# 07-I225-2.net
KiCad netlist of a schematic drawn in Altium Designer
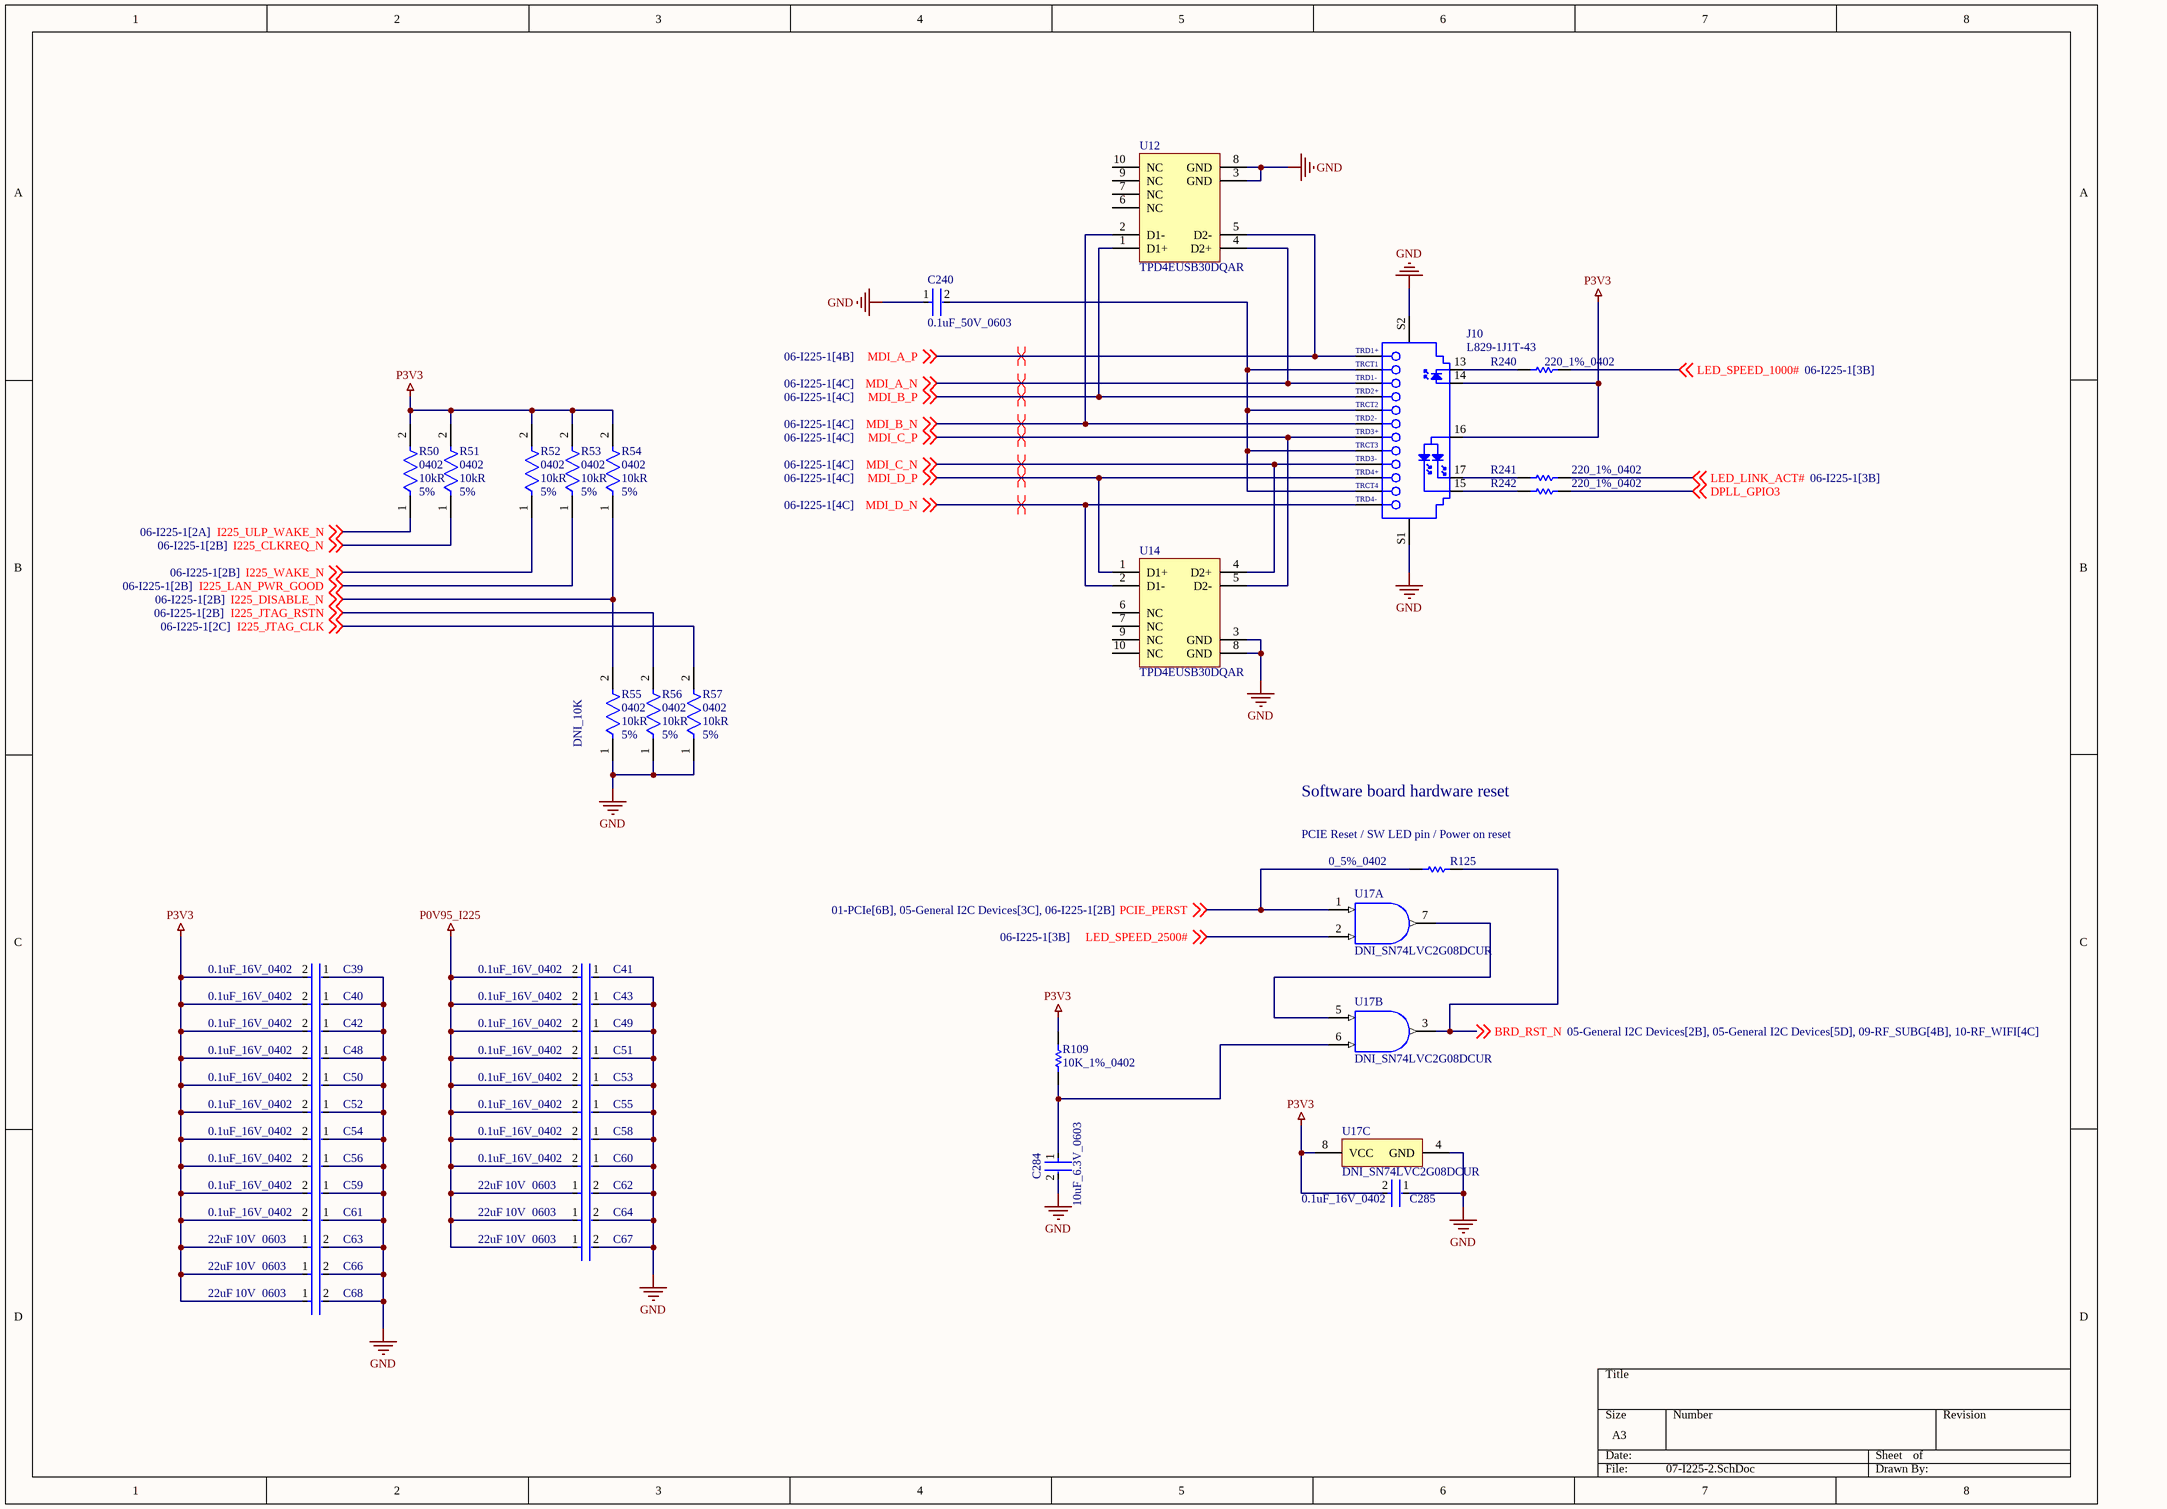
[diagram p0: 07-I225-2.SchDoc]

(export (version "E")
  (design (tool "Eeschema 10.0.6"))
  (components
    (comp (ref "C39")
      (value "0.1uF_16V_0402")
      (footprint "FP-GRM15-MFG")
      (description "CAP CER 0.1UF 16V X7R 0402")
      (fields (field (name "MANUFACTURER PART NUMBER") "GRM155R71C104KA88D") (field (name "TOLERANCE") "10%"))
      (libsource (lib "Altium Content Vault") (part "236180d848d6139a670b325ea6854c9"))
    )
    (comp (ref "C40")
      (value "0.1uF_16V_0402")
      (footprint "FP-GRM15-MFG")
      (description "CAP CER 0.1UF 16V X7R 0402")
      (fields (field (name "MANUFACTURER PART NUMBER") "GRM155R71C104KA88D") (field (name "TOLERANCE") "10%"))
      (libsource (lib "Altium Content Vault") (part "236180d848d6139a670b325ea6854c9"))
    )
    (comp (ref "C41")
      (value "0.1uF_16V_0402")
      (footprint "FP-GRM15-MFG")
      (description "CAP CER 0.1UF 16V X7R 0402")
      (fields (field (name "MANUFACTURER PART NUMBER") "GRM155R71C104KA88D") (field (name "TOLERANCE") "10%"))
      (libsource (lib "Altium Content Vault") (part "236180d848d6139a670b325ea6854c9"))
    )
    (comp (ref "C42")
      (value "0.1uF_16V_0402")
      (footprint "FP-GRM15-MFG")
      (description "CAP CER 0.1UF 16V X7R 0402")
      (fields (field (name "MANUFACTURER PART NUMBER") "GRM155R71C104KA88D") (field (name "TOLERANCE") "10%"))
      (libsource (lib "Altium Content Vault") (part "236180d848d6139a670b325ea6854c9"))
    )
    (comp (ref "C43")
      (value "0.1uF_16V_0402")
      (footprint "FP-GRM15-MFG")
      (description "CAP CER 0.1UF 16V X7R 0402")
      (fields (field (name "MANUFACTURER PART NUMBER") "GRM155R71C104KA88D") (field (name "TOLERANCE") "10%"))
      (libsource (lib "Altium Content Vault") (part "236180d848d6139a670b325ea6854c9"))
    )
    (comp (ref "C48")
      (value "0.1uF_16V_0402")
      (footprint "FP-GRM15-MFG")
      (description "CAP CER 0.1UF 16V X7R 0402")
      (fields (field (name "MANUFACTURER PART NUMBER") "GRM155R71C104KA88D") (field (name "TOLERANCE") "10%"))
      (libsource (lib "Altium Content Vault") (part "236180d848d6139a670b325ea6854c9"))
    )
    (comp (ref "C49")
      (value "0.1uF_16V_0402")
      (footprint "FP-GRM15-MFG")
      (description "CAP CER 0.1UF 16V X7R 0402")
      (fields (field (name "MANUFACTURER PART NUMBER") "GRM155R71C104KA88D") (field (name "TOLERANCE") "10%"))
      (libsource (lib "Altium Content Vault") (part "236180d848d6139a670b325ea6854c9"))
    )
    (comp (ref "C50")
      (value "0.1uF_16V_0402")
      (footprint "FP-GRM15-MFG")
      (description "CAP CER 0.1UF 16V X7R 0402")
      (fields (field (name "MANUFACTURER PART NUMBER") "GRM155R71C104KA88D") (field (name "TOLERANCE") "10%"))
      (libsource (lib "Altium Content Vault") (part "236180d848d6139a670b325ea6854c9"))
    )
    (comp (ref "C51")
      (value "0.1uF_16V_0402")
      (footprint "FP-GRM15-MFG")
      (description "CAP CER 0.1UF 16V X7R 0402")
      (fields (field (name "MANUFACTURER PART NUMBER") "GRM155R71C104KA88D") (field (name "TOLERANCE") "10%"))
      (libsource (lib "Altium Content Vault") (part "236180d848d6139a670b325ea6854c9"))
    )
    (comp (ref "C52")
      (value "0.1uF_16V_0402")
      (footprint "FP-GRM15-MFG")
      (description "CAP CER 0.1UF 16V X7R 0402")
      (fields (field (name "MANUFACTURER PART NUMBER") "GRM155R71C104KA88D") (field (name "TOLERANCE") "10%"))
      (libsource (lib "Altium Content Vault") (part "236180d848d6139a670b325ea6854c9"))
    )
    (comp (ref "C53")
      (value "0.1uF_16V_0402")
      (footprint "FP-GRM15-MFG")
      (description "CAP CER 0.1UF 16V X7R 0402")
      (fields (field (name "MANUFACTURER PART NUMBER") "GRM155R71C104KA88D") (field (name "TOLERANCE") "10%"))
      (libsource (lib "Altium Content Vault") (part "236180d848d6139a670b325ea6854c9"))
    )
    (comp (ref "C54")
      (value "0.1uF_16V_0402")
      (footprint "FP-GRM15-MFG")
      (description "CAP CER 0.1UF 16V X7R 0402")
      (fields (field (name "MANUFACTURER PART NUMBER") "GRM155R71C104KA88D") (field (name "TOLERANCE") "10%"))
      (libsource (lib "Altium Content Vault") (part "236180d848d6139a670b325ea6854c9"))
    )
    (comp (ref "C55")
      (value "0.1uF_16V_0402")
      (footprint "FP-GRM15-MFG")
      (description "CAP CER 0.1UF 16V X7R 0402")
      (fields (field (name "MANUFACTURER PART NUMBER") "GRM155R71C104KA88D") (field (name "TOLERANCE") "10%"))
      (libsource (lib "Altium Content Vault") (part "236180d848d6139a670b325ea6854c9"))
    )
    (comp (ref "C56")
      (value "0.1uF_16V_0402")
      (footprint "FP-GRM15-MFG")
      (description "CAP CER 0.1UF 16V X7R 0402")
      (fields (field (name "MANUFACTURER PART NUMBER") "GRM155R71C104KA88D") (field (name "TOLERANCE") "10%"))
      (libsource (lib "Altium Content Vault") (part "236180d848d6139a670b325ea6854c9"))
    )
    (comp (ref "C58")
      (value "0.1uF_16V_0402")
      (footprint "FP-GRM15-MFG")
      (description "CAP CER 0.1UF 16V X7R 0402")
      (fields (field (name "MANUFACTURER PART NUMBER") "GRM155R71C104KA88D") (field (name "TOLERANCE") "10%"))
      (libsource (lib "Altium Content Vault") (part "236180d848d6139a670b325ea6854c9"))
    )
    (comp (ref "C59")
      (value "0.1uF_16V_0402")
      (footprint "FP-GRM15-MFG")
      (description "CAP CER 0.1UF 16V X7R 0402")
      (fields (field (name "MANUFACTURER PART NUMBER") "GRM155R71C104KA88D") (field (name "TOLERANCE") "10%"))
      (libsource (lib "Altium Content Vault") (part "236180d848d6139a670b325ea6854c9"))
    )
    (comp (ref "C60")
      (value "0.1uF_16V_0402")
      (footprint "FP-GRM15-MFG")
      (description "CAP CER 0.1UF 16V X7R 0402")
      (fields (field (name "MANUFACTURER PART NUMBER") "GRM155R71C104KA88D") (field (name "TOLERANCE") "10%"))
      (libsource (lib "Altium Content Vault") (part "236180d848d6139a670b325ea6854c9"))
    )
    (comp (ref "C61")
      (value "0.1uF_16V_0402")
      (footprint "FP-GRM15-MFG")
      (description "CAP CER 0.1UF 16V X7R 0402")
      (fields (field (name "MANUFACTURER PART NUMBER") "GRM155R71C104KA88D") (field (name "TOLERANCE") "10%"))
      (libsource (lib "Altium Content Vault") (part "236180d848d6139a670b325ea6854c9"))
    )
    (comp (ref "C62")
      (value "GRM188R61A226ME15D")
      (footprint "FP-GRM188-0_2-IPC_C")
      (description "Chip Multilayer Ceramic Capacitors for General Purpose, 0603, 22uF, X5R, 15%, 20%, 10V")
      (fields
        (field (name "TOLERANCE") "20%")
        (field (name "CAPACITANCE") "22uF")
        (field (name "VOLTAGE RATING") "10V")
        (field (name "CASE CODE (IMPERIAL)") "0603")
      )
      (libsource (lib "Altium Content Vault") (part "11868f565c42a9108669ba33697ecf6"))
    )
    (comp (ref "C63")
      (value "GRM188R61A226ME15D")
      (footprint "FP-GRM188-0_2-IPC_C")
      (description "Chip Multilayer Ceramic Capacitors for General Purpose, 0603, 22uF, X5R, 15%, 20%, 10V")
      (fields
        (field (name "TOLERANCE") "20%")
        (field (name "CAPACITANCE") "22uF")
        (field (name "VOLTAGE RATING") "10V")
        (field (name "CASE CODE (IMPERIAL)") "0603")
      )
      (libsource (lib "Altium Content Vault") (part "11868f565c42a9108669ba33697ecf6"))
    )
    (comp (ref "C64")
      (value "GRM188R61A226ME15D")
      (footprint "FP-GRM188-0_2-IPC_C")
      (description "Chip Multilayer Ceramic Capacitors for General Purpose, 0603, 22uF, X5R, 15%, 20%, 10V")
      (fields
        (field (name "TOLERANCE") "20%")
        (field (name "CAPACITANCE") "22uF")
        (field (name "VOLTAGE RATING") "10V")
        (field (name "CASE CODE (IMPERIAL)") "0603")
      )
      (libsource (lib "Altium Content Vault") (part "11868f565c42a9108669ba33697ecf6"))
    )
    (comp (ref "C66")
      (value "GRM188R61A226ME15D")
      (footprint "FP-GRM188-0_2-IPC_C")
      (description "Chip Multilayer Ceramic Capacitors for General Purpose, 0603, 22uF, X5R, 15%, 20%, 10V")
      (fields
        (field (name "TOLERANCE") "20%")
        (field (name "CAPACITANCE") "22uF")
        (field (name "VOLTAGE RATING") "10V")
        (field (name "CASE CODE (IMPERIAL)") "0603")
      )
      (libsource (lib "Altium Content Vault") (part "11868f565c42a9108669ba33697ecf6"))
    )
    (comp (ref "C67")
      (value "GRM188R61A226ME15D")
      (footprint "FP-GRM188-0_2-IPC_C")
      (description "Chip Multilayer Ceramic Capacitors for General Purpose, 0603, 22uF, X5R, 15%, 20%, 10V")
      (fields
        (field (name "TOLERANCE") "20%")
        (field (name "CAPACITANCE") "22uF")
        (field (name "VOLTAGE RATING") "10V")
        (field (name "CASE CODE (IMPERIAL)") "0603")
      )
      (libsource (lib "Altium Content Vault") (part "11868f565c42a9108669ba33697ecf6"))
    )
    (comp (ref "C68")
      (value "GRM188R61A226ME15D")
      (footprint "FP-GRM188-0_2-IPC_C")
      (description "Chip Multilayer Ceramic Capacitors for General Purpose, 0603, 22uF, X5R, 15%, 20%, 10V")
      (fields
        (field (name "TOLERANCE") "20%")
        (field (name "CAPACITANCE") "22uF")
        (field (name "VOLTAGE RATING") "10V")
        (field (name "CASE CODE (IMPERIAL)") "0603")
      )
      (libsource (lib "Altium Content Vault") (part "11868f565c42a9108669ba33697ecf6"))
    )
    (comp (ref "C240")
      (value "0.1uF_50V_0603")
      (footprint "FP-C0603-CJ-MFG")
      (description "CAP CER 0.1UF 50V X7R 0603")
      (fields (field (name "MANUFACTURER PART NUMBER") "C0603X104K5RACTU") (field (name "VOLTAGE") "50V"))
      (libsource (lib "Altium Content Vault") (part "11868f565c42a9108669ba33697ecf6"))
    )
    (comp (ref "C284")
      (value "10uF_6.3V_0603")
      (footprint "FP-C0603C106M9PACTU-MFG")
      (description "CAP CER 10UF 6.3V X5R 0603")
      (fields
        (field (name "MANUFACTURER PART NUMBER") "C0603C106M9PACTU")
        (field (name "MANUFACTURER") "Kemet")
      )
      (libsource (lib "Altium Content Vault") (part "b4654b650e69147ec39a6b967a45e02"))
    )
    (comp (ref "C285")
      (value "0.1uF_16V_0402")
      (footprint "FP-GRM15-MFG")
      (description "CAP CER 0.1UF 16V X7R 0402")
      (fields (field (name "MANUFACTURER PART NUMBER") "GRM155R71C104KA88D") (field (name "TOLERANCE") "10%"))
      (libsource (lib "Altium Content Vault") (part "236180d848d6139a670b325ea6854c9"))
    )
    (comp (ref "J10")
      (value "L829-1J1T-43")
      (footprint "BELS-L829-1J1T-43_V")
      (description "Gigabit MagJack(R) Ultra Low Profile, 10/100/1000 Base-T, 19-Pin THD, RoHS, Tray")
      (libsource (lib "Altium Content Vault") (part "RJ45-17-2SHLD"))
    )
    (comp (ref "R50")
      (value "CRCW040210K0JNED")
      (footprint "FP-CRCW0402-e3-IPC_B")
      (description "RES Thick Film, 10kΩ, 5%, 0.063W, 200ppm/°C, 0402")
      (fields
        (field (name "CASE/PACKAGE") "0402")
        (field (name "RESISTANCE") "10kR")
        (field (name "TOLERANCE") "5%")
      )
      (libsource (lib "Altium Content Vault") (part "1029c3af85768c4190bb7ad29bc67b5"))
    )
    (comp (ref "R51")
      (value "CRCW040210K0JNED")
      (footprint "FP-CRCW0402-e3-IPC_B")
      (description "RES Thick Film, 10kΩ, 5%, 0.063W, 200ppm/°C, 0402")
      (fields
        (field (name "CASE/PACKAGE") "0402")
        (field (name "RESISTANCE") "10kR")
        (field (name "TOLERANCE") "5%")
      )
      (libsource (lib "Altium Content Vault") (part "1029c3af85768c4190bb7ad29bc67b5"))
    )
    (comp (ref "R52")
      (value "CRCW040210K0JNED")
      (footprint "FP-CRCW0402-e3-IPC_B")
      (description "RES Thick Film, 10kΩ, 5%, 0.063W, 200ppm/°C, 0402")
      (fields
        (field (name "CASE/PACKAGE") "0402")
        (field (name "RESISTANCE") "10kR")
        (field (name "TOLERANCE") "5%")
      )
      (libsource (lib "Altium Content Vault") (part "1029c3af85768c4190bb7ad29bc67b5"))
    )
    (comp (ref "R53")
      (value "CRCW040210K0JNED")
      (footprint "FP-CRCW0402-e3-IPC_B")
      (description "RES Thick Film, 10kΩ, 5%, 0.063W, 200ppm/°C, 0402")
      (fields
        (field (name "CASE/PACKAGE") "0402")
        (field (name "RESISTANCE") "10kR")
        (field (name "TOLERANCE") "5%")
      )
      (libsource (lib "Altium Content Vault") (part "1029c3af85768c4190bb7ad29bc67b5"))
    )
    (comp (ref "R54")
      (value "CRCW040210K0JNED")
      (footprint "FP-CRCW0402-e3-IPC_B")
      (description "RES Thick Film, 10kΩ, 5%, 0.063W, 200ppm/°C, 0402")
      (fields
        (field (name "CASE/PACKAGE") "0402")
        (field (name "RESISTANCE") "10kR")
        (field (name "TOLERANCE") "5%")
      )
      (libsource (lib "Altium Content Vault") (part "1029c3af85768c4190bb7ad29bc67b5"))
    )
    (comp (ref "R55")
      (value "DNI_10K")
      (footprint "FP-CRCW0402-e3-IPC_B")
      (description "RES Thick Film, 10kΩ, 5%, 0.063W, 200ppm/°C, 0402")
      (fields
        (field (name "CASE/PACKAGE") "0402")
        (field (name "RESISTANCE") "10kR")
        (field (name "TOLERANCE") "5%")
      )
      (libsource (lib "Altium Content Vault") (part "1029c3af85768c4190bb7ad29bc67b5"))
    )
    (comp (ref "R56")
      (value "CRCW040210K0JNED")
      (footprint "FP-CRCW0402-e3-IPC_B")
      (description "RES Thick Film, 10kΩ, 5%, 0.063W, 200ppm/°C, 0402")
      (fields
        (field (name "CASE/PACKAGE") "0402")
        (field (name "RESISTANCE") "10kR")
        (field (name "TOLERANCE") "5%")
      )
      (libsource (lib "Altium Content Vault") (part "1029c3af85768c4190bb7ad29bc67b5"))
    )
    (comp (ref "R57")
      (value "CRCW040210K0JNED")
      (footprint "FP-CRCW0402-e3-IPC_B")
      (description "RES Thick Film, 10kΩ, 5%, 0.063W, 200ppm/°C, 0402")
      (fields
        (field (name "CASE/PACKAGE") "0402")
        (field (name "RESISTANCE") "10kR")
        (field (name "TOLERANCE") "5%")
      )
      (libsource (lib "Altium Content Vault") (part "1029c3af85768c4190bb7ad29bc67b5"))
    )
    (comp (ref "R109")
      (value "10K_1%_0402")
      (footprint "RESC1005X40X25NL10T10")
      (fields (field (name "MANUFACTURER") "Bourns") (field (name "PART NUMBER") "CR0402-FX-1002GLF"))
      (libsource (lib "Altium Content Vault") (part "RES"))
    )
    (comp (ref "R125")
      (value "0_5%_0402")
      (footprint "RESC1005X40X25LL10T10")
      (fields (field (name "MANUFACTURER") "KOA Speer") (field (name "PART NUMBER") "RK73Z1ETTP"))
      (libsource (lib "Altium Content Vault") (part "RES"))
    )
    (comp (ref "R240")
      (value "220_1%_0402")
      (footprint "RESC1005X40X25LL10T10")
      (fields (field (name "PART NUMBER") "RK73H1ETTP2200F") (field (name "MANUFACTURER") "KOA Speer"))
      (libsource (lib "Altium Content Vault") (part "RES"))
    )
    (comp (ref "R241")
      (value "220_1%_0402")
      (footprint "RESC1005X40X25LL10T10")
      (fields (field (name "PART NUMBER") "RK73H1ETTP2200F") (field (name "MANUFACTURER") "KOA Speer"))
      (libsource (lib "Altium Content Vault") (part "RES"))
    )
    (comp (ref "R242")
      (value "220_1%_0402")
      (footprint "RESC1005X40X25LL10T10")
      (fields (field (name "PART NUMBER") "RK73H1ETTP2200F") (field (name "MANUFACTURER") "KOA Speer"))
      (libsource (lib "Altium Content Vault") (part "RES"))
    )
    (comp (ref "U12")
      (value "TPD4EUSB30DQAR")
      (footprint "DQA0010A_V")
      (fields (field (name "MANUFACTURER") "Texas Instruments"))
      (libsource (lib "") (part "TI-TPD4EUSB30-SON_DQA-10_1"))
    )
    (comp (ref "U14")
      (value "TPD4EUSB30DQAR")
      (footprint "DQA0010A_V")
      (fields (field (name "MANUFACTURER") "Texas Instruments"))
      (libsource (lib "Altium Content Vault") (part "TI-TPD4EUSB30-SON_DQA-10"))
    )
    (comp (ref "U17")
      (value "DNI_SN74LVC2G08DCUR")
      (footprint "DCU0008A_M")
      (description "Dual 2-Input Positive-AND Gate, DCU0008A, LARGE T&R")
      (fields
        (field (name "MANUFACTURER") "Texas Instruments")
        (field (name "GENERIC PART NUMBER") "SN74LVC2G08")
      )
      (libsource (lib "Altium Content Vault") (part "TI-SN74XXX2G08-8"))
    )
  )
  (nets
    (net (code "1") (name "BRD_RST_N") (class "Default")
      (node (ref "R125") (pin "2") (pinfunction "2_2") (pintype "passive"))
      (node (ref "U17") (pin "3") (pinfunction "2Y_3") (pintype "output"))
    )
    (net (code "2") (name "DPLL_GPIO3") (class "Default")
      (node (ref "R242") (pin "2") (pinfunction "2_2") (pintype "passive"))
    )
    (net (code "3") (name "GND") (class "Default")
      (node (ref "C240") (pin "1") (pinfunction "1_1") (pintype "passive"))
      (node (ref "C284") (pin "2") (pinfunction "2_2") (pintype "passive"))
      (node (ref "C285") (pin "1") (pinfunction "1_1") (pintype "passive"))
      (node (ref "C39") (pin "1") (pinfunction "1_1") (pintype "passive"))
      (node (ref "C40") (pin "1") (pinfunction "1_1") (pintype "passive"))
      (node (ref "C41") (pin "1") (pinfunction "1_1") (pintype "passive"))
      (node (ref "C42") (pin "1") (pinfunction "1_1") (pintype "passive"))
      (node (ref "C43") (pin "1") (pinfunction "1_1") (pintype "passive"))
      (node (ref "C48") (pin "1") (pinfunction "1_1") (pintype "passive"))
      (node (ref "C49") (pin "1") (pinfunction "1_1") (pintype "passive"))
      (node (ref "C50") (pin "1") (pinfunction "1_1") (pintype "passive"))
      (node (ref "C51") (pin "1") (pinfunction "1_1") (pintype "passive"))
      (node (ref "C52") (pin "1") (pinfunction "1_1") (pintype "passive"))
      (node (ref "C53") (pin "1") (pinfunction "1_1") (pintype "passive"))
      (node (ref "C54") (pin "1") (pinfunction "1_1") (pintype "passive"))
      (node (ref "C55") (pin "1") (pinfunction "1_1") (pintype "passive"))
      (node (ref "C56") (pin "1") (pinfunction "1_1") (pintype "passive"))
      (node (ref "C58") (pin "1") (pinfunction "1_1") (pintype "passive"))
      (node (ref "C59") (pin "1") (pinfunction "1_1") (pintype "passive"))
      (node (ref "C60") (pin "1") (pinfunction "1_1") (pintype "passive"))
      (node (ref "C61") (pin "1") (pinfunction "1_1") (pintype "passive"))
      (node (ref "C62") (pin "2") (pinfunction "2_2") (pintype "passive"))
      (node (ref "C63") (pin "2") (pinfunction "2_2") (pintype "passive"))
      (node (ref "C64") (pin "2") (pinfunction "2_2") (pintype "passive"))
      (node (ref "C66") (pin "2") (pinfunction "2_2") (pintype "passive"))
      (node (ref "C67") (pin "2") (pinfunction "2_2") (pintype "passive"))
      (node (ref "C68") (pin "2") (pinfunction "2_2") (pintype "passive"))
      (node (ref "J10") (pin "S1") (pinfunction "S1_S1") (pintype "passive"))
      (node (ref "J10") (pin "S2") (pinfunction "S2_S2") (pintype "passive"))
      (node (ref "R55") (pin "1") (pinfunction "1_1") (pintype "passive"))
      (node (ref "R56") (pin "1") (pinfunction "1_1") (pintype "passive"))
      (node (ref "R57") (pin "1") (pinfunction "1_1") (pintype "passive"))
      (node (ref "U12") (pin "3") (pinfunction "GND_3") (pintype "power_in"))
      (node (ref "U12") (pin "8") (pinfunction "GND_8") (pintype "power_in"))
      (node (ref "U14") (pin "3") (pinfunction "GND_3") (pintype "power_in"))
      (node (ref "U14") (pin "8") (pinfunction "GND_8") (pintype "power_in"))
      (node (ref "U17") (pin "4") (pinfunction "GND_4") (pintype "power_in"))
    )
    (net (code "4") (name "I225_CLKREQ_N") (class "Default")
      (node (ref "R51") (pin "1") (pinfunction "1_1") (pintype "passive"))
    )
    (net (code "5") (name "I225_DISABLE_N") (class "Default")
      (node (ref "R54") (pin "1") (pinfunction "1_1") (pintype "passive"))
      (node (ref "R55") (pin "2") (pinfunction "2_2") (pintype "passive"))
    )
    (net (code "6") (name "I225_JTAG_CLK") (class "Default")
      (node (ref "R57") (pin "2") (pinfunction "2_2") (pintype "passive"))
    )
    (net (code "7") (name "I225_JTAG_RSTN") (class "Default")
      (node (ref "R56") (pin "2") (pinfunction "2_2") (pintype "passive"))
    )
    (net (code "8") (name "I225_LAN_PWR_GOOD") (class "Default")
      (node (ref "R53") (pin "1") (pinfunction "1_1") (pintype "passive"))
    )
    (net (code "9") (name "I225_ULP_WAKE_N") (class "Default")
      (node (ref "R50") (pin "1") (pinfunction "1_1") (pintype "passive"))
    )
    (net (code "10") (name "I225_WAKE_N") (class "Default")
      (node (ref "R52") (pin "1") (pinfunction "1_1") (pintype "passive"))
    )
    (net (code "11") (name "LED_LINK_ACT#") (class "Default")
      (node (ref "R241") (pin "2") (pinfunction "2_2") (pintype "passive"))
    )
    (net (code "12") (name "LED_SPEED_1000#") (class "Default")
      (node (ref "R240") (pin "2") (pinfunction "2_2") (pintype "passive"))
    )
    (net (code "13") (name "LED_SPEED_2500#") (class "Default")
      (node (ref "U17") (pin "2") (pinfunction "1B_2") (pintype "input"))
    )
    (net (code "14") (name "MDI_A_N") (class "Default")
      (node (ref "J10") (pin "3") (pinfunction "TRD1-_3") (pintype "passive"))
      (node (ref "U12") (pin "4") (pinfunction "D2+_4") (pintype "passive"))
    )
    (net (code "15") (name "MDI_A_P") (class "Default")
      (node (ref "J10") (pin "1") (pinfunction "TRD1+_1") (pintype "passive"))
      (node (ref "U12") (pin "5") (pinfunction "D2-_5") (pintype "passive"))
    )
    (net (code "16") (name "MDI_B_N") (class "Default")
      (node (ref "J10") (pin "6") (pinfunction "TRD2-_6") (pintype "passive"))
      (node (ref "U12") (pin "2") (pinfunction "D1-_2") (pintype "passive"))
    )
    (net (code "17") (name "MDI_B_P") (class "Default")
      (node (ref "J10") (pin "4") (pinfunction "TRD2+_4") (pintype "passive"))
      (node (ref "U12") (pin "1") (pinfunction "D1+_1") (pintype "passive"))
    )
    (net (code "18") (name "MDI_C_N") (class "Default")
      (node (ref "J10") (pin "9") (pinfunction "TRD3-_9") (pintype "passive"))
      (node (ref "U14") (pin "4") (pinfunction "D2+_4") (pintype "passive"))
    )
    (net (code "19") (name "MDI_C_P") (class "Default")
      (node (ref "J10") (pin "7") (pinfunction "TRD3+_7") (pintype "passive"))
      (node (ref "U14") (pin "5") (pinfunction "D2-_5") (pintype "passive"))
    )
    (net (code "20") (name "MDI_D_N") (class "Default")
      (node (ref "J10") (pin "12") (pinfunction "TRD4-_12") (pintype "passive"))
      (node (ref "U14") (pin "2") (pinfunction "D1-_2") (pintype "passive"))
    )
    (net (code "21") (name "MDI_D_P") (class "Default")
      (node (ref "J10") (pin "10") (pinfunction "TRD4+_10") (pintype "passive"))
      (node (ref "U14") (pin "1") (pinfunction "D1+_1") (pintype "passive"))
    )
    (net (code "22") (name "Net-(J10-Pad13)") (class "Default")
      (node (ref "J10") (pin "13") (pinfunction "13_13") (pintype "passive"))
      (node (ref "R240") (pin "1") (pinfunction "1_1") (pintype "passive"))
    )
    (net (code "23") (name "Net-(J10-Pad15)") (class "Default")
      (node (ref "J10") (pin "15") (pinfunction "15_15") (pintype "passive"))
      (node (ref "R242") (pin "1") (pinfunction "1_1") (pintype "passive"))
    )
    (net (code "24") (name "Net-(J10-Pad17)") (class "Default")
      (node (ref "J10") (pin "17") (pinfunction "17_17") (pintype "passive"))
      (node (ref "R241") (pin "1") (pinfunction "1_1") (pintype "passive"))
    )
    (net (code "25") (name "Net-(J10-TRCT1)") (class "Default")
      (node (ref "C240") (pin "2") (pinfunction "2_2") (pintype "passive"))
      (node (ref "J10") (pin "11") (pinfunction "TRCT4_11") (pintype "passive"))
      (node (ref "J10") (pin "2") (pinfunction "TRCT1_2") (pintype "passive"))
      (node (ref "J10") (pin "5") (pinfunction "TRCT2_5") (pintype "passive"))
      (node (ref "J10") (pin "8") (pinfunction "TRCT3_8") (pintype "passive"))
    )
    (net (code "26") (name "Net-(U17A-1Y)") (class "Default")
      (node (ref "U17") (pin "5") (pinfunction "2A_5") (pintype "input"))
      (node (ref "U17") (pin "7") (pinfunction "1Y_7") (pintype "output"))
    )
    (net (code "27") (name "Net-(U17B-2B)") (class "Default")
      (node (ref "C284") (pin "1") (pinfunction "1_1") (pintype "passive"))
      (node (ref "R109") (pin "1") (pinfunction "1_1") (pintype "passive"))
      (node (ref "U17") (pin "6") (pinfunction "2B_6") (pintype "input"))
    )
    (net (code "28") (name "P0V95_I225") (class "Default")
      (node (ref "C41") (pin "2") (pinfunction "2_2") (pintype "passive"))
      (node (ref "C43") (pin "2") (pinfunction "2_2") (pintype "passive"))
      (node (ref "C49") (pin "2") (pinfunction "2_2") (pintype "passive"))
      (node (ref "C51") (pin "2") (pinfunction "2_2") (pintype "passive"))
      (node (ref "C53") (pin "2") (pinfunction "2_2") (pintype "passive"))
      (node (ref "C55") (pin "2") (pinfunction "2_2") (pintype "passive"))
      (node (ref "C58") (pin "2") (pinfunction "2_2") (pintype "passive"))
      (node (ref "C60") (pin "2") (pinfunction "2_2") (pintype "passive"))
      (node (ref "C62") (pin "1") (pinfunction "1_1") (pintype "passive"))
      (node (ref "C64") (pin "1") (pinfunction "1_1") (pintype "passive"))
      (node (ref "C67") (pin "1") (pinfunction "1_1") (pintype "passive"))
    )
    (net (code "29") (name "P3V3") (class "Default")
      (node (ref "C285") (pin "2") (pinfunction "2_2") (pintype "passive"))
      (node (ref "C39") (pin "2") (pinfunction "2_2") (pintype "passive"))
      (node (ref "C40") (pin "2") (pinfunction "2_2") (pintype "passive"))
      (node (ref "C42") (pin "2") (pinfunction "2_2") (pintype "passive"))
      (node (ref "C48") (pin "2") (pinfunction "2_2") (pintype "passive"))
      (node (ref "C50") (pin "2") (pinfunction "2_2") (pintype "passive"))
      (node (ref "C52") (pin "2") (pinfunction "2_2") (pintype "passive"))
      (node (ref "C54") (pin "2") (pinfunction "2_2") (pintype "passive"))
      (node (ref "C56") (pin "2") (pinfunction "2_2") (pintype "passive"))
      (node (ref "C59") (pin "2") (pinfunction "2_2") (pintype "passive"))
      (node (ref "C61") (pin "2") (pinfunction "2_2") (pintype "passive"))
      (node (ref "C63") (pin "1") (pinfunction "1_1") (pintype "passive"))
      (node (ref "C66") (pin "1") (pinfunction "1_1") (pintype "passive"))
      (node (ref "C68") (pin "1") (pinfunction "1_1") (pintype "passive"))
      (node (ref "J10") (pin "14") (pinfunction "14_14") (pintype "passive"))
      (node (ref "J10") (pin "16") (pinfunction "16_16") (pintype "passive"))
      (node (ref "R109") (pin "2") (pinfunction "2_2") (pintype "passive"))
      (node (ref "R50") (pin "2") (pinfunction "2_2") (pintype "passive"))
      (node (ref "R51") (pin "2") (pinfunction "2_2") (pintype "passive"))
      (node (ref "R52") (pin "2") (pinfunction "2_2") (pintype "passive"))
      (node (ref "R53") (pin "2") (pinfunction "2_2") (pintype "passive"))
      (node (ref "R54") (pin "2") (pinfunction "2_2") (pintype "passive"))
      (node (ref "U17") (pin "8") (pinfunction "VCC_8") (pintype "power_in"))
    )
    (net (code "30") (name "PCIE_PERST") (class "Default")
      (node (ref "R125") (pin "1") (pinfunction "1_1") (pintype "passive"))
      (node (ref "U17") (pin "1") (pinfunction "1A_1") (pintype "input"))
    )
    (net (code "31") (name "unconnected-(U12-NC-Pad6)") (class "Default")
      (node (ref "U12") (pin "6") (pinfunction "NC_6") (pintype "passive"))
    )
    (net (code "32") (name "unconnected-(U12-NC-Pad7)") (class "Default")
      (node (ref "U12") (pin "7") (pinfunction "NC_7") (pintype "passive"))
    )
    (net (code "33") (name "unconnected-(U12-NC-Pad9)") (class "Default")
      (node (ref "U12") (pin "9") (pinfunction "NC_9") (pintype "passive"))
    )
    (net (code "34") (name "unconnected-(U12-NC-Pad10)") (class "Default")
      (node (ref "U12") (pin "10") (pinfunction "NC_10") (pintype "passive"))
    )
    (net (code "35") (name "unconnected-(U14-NC-Pad6)") (class "Default")
      (node (ref "U14") (pin "6") (pinfunction "NC_6") (pintype "passive"))
    )
    (net (code "36") (name "unconnected-(U14-NC-Pad7)") (class "Default")
      (node (ref "U14") (pin "7") (pinfunction "NC_7") (pintype "passive"))
    )
    (net (code "37") (name "unconnected-(U14-NC-Pad9)") (class "Default")
      (node (ref "U14") (pin "9") (pinfunction "NC_9") (pintype "passive"))
    )
    (net (code "38") (name "unconnected-(U14-NC-Pad10)") (class "Default")
      (node (ref "U14") (pin "10") (pinfunction "NC_10") (pintype "passive"))
    )
  )
)
